# pcb.net
KiCad netlist of a schematic drawn in EAGLE
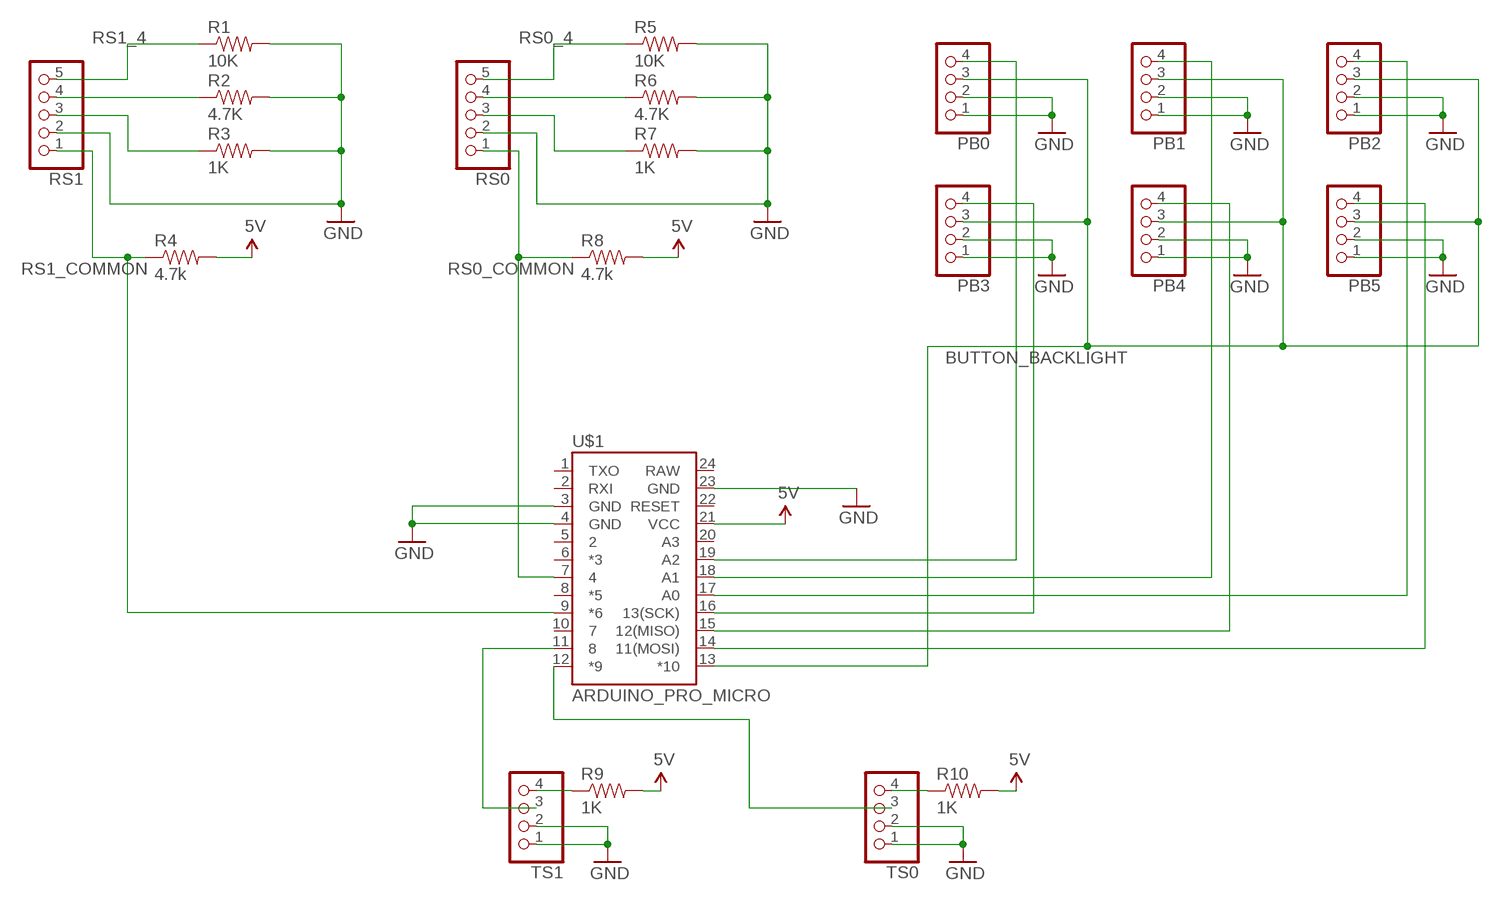
[diagram p0: schematic, sheet 1]

(export (version "E")
  (design (tool "Eeschema 10.0.6"))
  (components
    (comp (ref "PB0")
      (value "PINHD-1X4")
      (footprint "eagle-import:1X04")
      (libsource (lib "eagle-import") (part "PINHD-1X4"))
    )
    (comp (ref "PB1")
      (value "PINHD-1X4")
      (footprint "eagle-import:1X04")
      (libsource (lib "eagle-import") (part "PINHD-1X4"))
    )
    (comp (ref "PB2")
      (value "PINHD-1X4")
      (footprint "eagle-import:1X04")
      (libsource (lib "eagle-import") (part "PINHD-1X4"))
    )
    (comp (ref "PB3")
      (value "PINHD-1X4")
      (footprint "eagle-import:1X04")
      (libsource (lib "eagle-import") (part "PINHD-1X4"))
    )
    (comp (ref "PB4")
      (value "PINHD-1X4")
      (footprint "eagle-import:1X04")
      (libsource (lib "eagle-import") (part "PINHD-1X4"))
    )
    (comp (ref "PB5")
      (value "PINHD-1X4")
      (footprint "eagle-import:1X04")
      (libsource (lib "eagle-import") (part "PINHD-1X4"))
    )
    (comp (ref "R1")
      (value "10K")
      (footprint "eagle-import:AXIAL-0.3EZ")
      (libsource (lib "eagle-import") (part "1KOHM-1/4W-1%(PTH)HORIZ-KIT"))
    )
    (comp (ref "R2")
      (value "4.7K")
      (footprint "eagle-import:AXIAL-0.3EZ")
      (libsource (lib "eagle-import") (part "1KOHM-1/4W-1%(PTH)HORIZ-KIT"))
    )
    (comp (ref "R3")
      (value "1K")
      (footprint "eagle-import:AXIAL-0.3EZ")
      (libsource (lib "eagle-import") (part "1KOHM-1/4W-1%(PTH)HORIZ-KIT"))
    )
    (comp (ref "R4")
      (value "4.7k")
      (footprint "eagle-import:AXIAL-0.3EZ")
      (libsource (lib "eagle-import") (part "1KOHM-1/4W-1%(PTH)HORIZ-KIT"))
    )
    (comp (ref "R5")
      (value "10K")
      (footprint "eagle-import:AXIAL-0.3EZ")
      (libsource (lib "eagle-import") (part "1KOHM-1/4W-1%(PTH)HORIZ-KIT"))
    )
    (comp (ref "R6")
      (value "4.7K")
      (footprint "eagle-import:AXIAL-0.3EZ")
      (libsource (lib "eagle-import") (part "1KOHM-1/4W-1%(PTH)HORIZ-KIT"))
    )
    (comp (ref "R7")
      (value "1K")
      (footprint "eagle-import:AXIAL-0.3EZ")
      (libsource (lib "eagle-import") (part "1KOHM-1/4W-1%(PTH)HORIZ-KIT"))
    )
    (comp (ref "R8")
      (value "4.7k")
      (footprint "eagle-import:AXIAL-0.3EZ")
      (libsource (lib "eagle-import") (part "1KOHM-1/4W-1%(PTH)HORIZ-KIT"))
    )
    (comp (ref "R9")
      (value "1K")
      (footprint "eagle-import:AXIAL-0.3EZ")
      (libsource (lib "eagle-import") (part "1KOHM-1/4W-1%(PTH)HORIZ-KIT"))
    )
    (comp (ref "R10")
      (value "1K")
      (footprint "eagle-import:AXIAL-0.3EZ")
      (libsource (lib "eagle-import") (part "1KOHM-1/4W-1%(PTH)HORIZ-KIT"))
    )
    (comp (ref "RS0")
      (value "PINHD-1X5")
      (footprint "eagle-import:1X05")
      (libsource (lib "eagle-import") (part "PINHD-1X5"))
    )
    (comp (ref "RS1")
      (value "PINHD-1X5")
      (footprint "eagle-import:1X05")
      (libsource (lib "eagle-import") (part "PINHD-1X5"))
    )
    (comp (ref "TS0")
      (value "PINHD-1X4")
      (footprint "eagle-import:1X04")
      (libsource (lib "eagle-import") (part "PINHD-1X4"))
    )
    (comp (ref "TS1")
      (value "PINHD-1X4")
      (footprint "eagle-import:1X04")
      (libsource (lib "eagle-import") (part "PINHD-1X4"))
    )
    (comp (ref "U$1")
      (value "ARDUINO_PRO_MICRO")
      (footprint "eagle-import:ARDUINO_PRO_MICRO")
      (libsource (lib "eagle-import") (part "ARDUINO_PRO_MICRO"))
    )
  )
  (nets
    (net (code "1") (name "/BUTTON_BACKLIGHT") (class "Default")
      (node (ref "PB0") (pin "3") (pinfunction "3_3") (pintype "passive"))
      (node (ref "PB1") (pin "3") (pinfunction "3_3") (pintype "passive"))
      (node (ref "PB2") (pin "3") (pinfunction "3_3") (pintype "passive"))
      (node (ref "PB3") (pin "3") (pinfunction "3_3") (pintype "passive"))
      (node (ref "PB4") (pin "3") (pinfunction "3_3") (pintype "passive"))
      (node (ref "PB5") (pin "3") (pinfunction "3_3") (pintype "passive"))
      (node (ref "U$1") (pin "13") (pinfunction "*10_13") (pintype "bidirectional"))
    )
    (net (code "2") (name "/RS0_4") (class "Default")
      (node (ref "R5") (pin "P$1") (pinfunction "1_P$1") (pintype "passive"))
      (node (ref "RS0") (pin "5") (pinfunction "5_5") (pintype "passive"))
    )
    (net (code "3") (name "/RS0_COMMON") (class "Default")
      (node (ref "R8") (pin "P$1") (pinfunction "1_P$1") (pintype "passive"))
      (node (ref "RS0") (pin "1") (pinfunction "1_1") (pintype "passive"))
      (node (ref "U$1") (pin "7") (pinfunction "4_7") (pintype "bidirectional"))
    )
    (net (code "4") (name "/RS1_4") (class "Default")
      (node (ref "R1") (pin "P$1") (pinfunction "1_P$1") (pintype "passive"))
      (node (ref "RS1") (pin "5") (pinfunction "5_5") (pintype "passive"))
    )
    (net (code "5") (name "/RS1_COMMON") (class "Default")
      (node (ref "R4") (pin "P$1") (pinfunction "1_P$1") (pintype "passive"))
      (node (ref "RS1") (pin "1") (pinfunction "1_1") (pintype "passive"))
      (node (ref "U$1") (pin "9") (pinfunction "*6_9") (pintype "bidirectional"))
    )
    (net (code "6") (name "5V") (class "Default")
      (node (ref "R10") (pin "P$2") (pinfunction "2_P$2") (pintype "passive"))
      (node (ref "R4") (pin "P$2") (pinfunction "2_P$2") (pintype "passive"))
      (node (ref "R8") (pin "P$2") (pinfunction "2_P$2") (pintype "passive"))
      (node (ref "R9") (pin "P$2") (pinfunction "2_P$2") (pintype "passive"))
      (node (ref "U$1") (pin "21") (pinfunction "VCC_21") (pintype "bidirectional"))
    )
    (net (code "7") (name "GND") (class "Default")
      (node (ref "PB0") (pin "1") (pinfunction "1_1") (pintype "passive"))
      (node (ref "PB0") (pin "2") (pinfunction "2_2") (pintype "passive"))
      (node (ref "PB1") (pin "1") (pinfunction "1_1") (pintype "passive"))
      (node (ref "PB1") (pin "2") (pinfunction "2_2") (pintype "passive"))
      (node (ref "PB2") (pin "1") (pinfunction "1_1") (pintype "passive"))
      (node (ref "PB2") (pin "2") (pinfunction "2_2") (pintype "passive"))
      (node (ref "PB3") (pin "1") (pinfunction "1_1") (pintype "passive"))
      (node (ref "PB3") (pin "2") (pinfunction "2_2") (pintype "passive"))
      (node (ref "PB4") (pin "1") (pinfunction "1_1") (pintype "passive"))
      (node (ref "PB4") (pin "2") (pinfunction "2_2") (pintype "passive"))
      (node (ref "PB5") (pin "1") (pinfunction "1_1") (pintype "passive"))
      (node (ref "PB5") (pin "2") (pinfunction "2_2") (pintype "passive"))
      (node (ref "R1") (pin "P$2") (pinfunction "2_P$2") (pintype "passive"))
      (node (ref "R2") (pin "P$2") (pinfunction "2_P$2") (pintype "passive"))
      (node (ref "R3") (pin "P$2") (pinfunction "2_P$2") (pintype "passive"))
      (node (ref "R5") (pin "P$2") (pinfunction "2_P$2") (pintype "passive"))
      (node (ref "R6") (pin "P$2") (pinfunction "2_P$2") (pintype "passive"))
      (node (ref "R7") (pin "P$2") (pinfunction "2_P$2") (pintype "passive"))
      (node (ref "RS0") (pin "2") (pinfunction "2_2") (pintype "passive"))
      (node (ref "RS1") (pin "2") (pinfunction "2_2") (pintype "passive"))
      (node (ref "TS0") (pin "1") (pinfunction "1_1") (pintype "passive"))
      (node (ref "TS0") (pin "2") (pinfunction "2_2") (pintype "passive"))
      (node (ref "TS1") (pin "1") (pinfunction "1_1") (pintype "passive"))
      (node (ref "TS1") (pin "2") (pinfunction "2_2") (pintype "passive"))
      (node (ref "U$1") (pin "23") (pinfunction "GND_23") (pintype "bidirectional"))
      (node (ref "U$1") (pin "3") (pinfunction "GND_3") (pintype "bidirectional"))
      (node (ref "U$1") (pin "4") (pinfunction "GND_4") (pintype "bidirectional"))
    )
    (net (code "8") (name "Net-(R2-1)") (class "Default")
      (node (ref "R2") (pin "P$1") (pinfunction "1_P$1") (pintype "passive"))
      (node (ref "RS1") (pin "4") (pinfunction "4_4") (pintype "passive"))
    )
    (net (code "9") (name "Net-(R3-1)") (class "Default")
      (node (ref "R3") (pin "P$1") (pinfunction "1_P$1") (pintype "passive"))
      (node (ref "RS1") (pin "3") (pinfunction "3_3") (pintype "passive"))
    )
    (net (code "10") (name "Net-(R6-1)") (class "Default")
      (node (ref "R6") (pin "P$1") (pinfunction "1_P$1") (pintype "passive"))
      (node (ref "RS0") (pin "4") (pinfunction "4_4") (pintype "passive"))
    )
    (net (code "11") (name "Net-(R7-1)") (class "Default")
      (node (ref "R7") (pin "P$1") (pinfunction "1_P$1") (pintype "passive"))
      (node (ref "RS0") (pin "3") (pinfunction "3_3") (pintype "passive"))
    )
    (net (code "12") (name "Net-(R9-1)") (class "Default")
      (node (ref "R9") (pin "P$1") (pinfunction "1_P$1") (pintype "passive"))
      (node (ref "TS1") (pin "4") (pinfunction "4_4") (pintype "passive"))
    )
    (net (code "13") (name "Net-(R10-1)") (class "Default")
      (node (ref "R10") (pin "P$1") (pinfunction "1_P$1") (pintype "passive"))
      (node (ref "TS0") (pin "4") (pinfunction "4_4") (pintype "passive"))
    )
    (net (code "14") (name "Net-(U$1-*9)") (class "Default")
      (node (ref "TS0") (pin "3") (pinfunction "3_3") (pintype "passive"))
      (node (ref "U$1") (pin "12") (pinfunction "*9_12") (pintype "bidirectional"))
    )
    (net (code "15") (name "Net-(U$1-8)") (class "Default")
      (node (ref "TS1") (pin "3") (pinfunction "3_3") (pintype "passive"))
      (node (ref "U$1") (pin "11") (pinfunction "8_11") (pintype "bidirectional"))
    )
    (net (code "16") (name "Net-(U$1-11(MOSI))") (class "Default")
      (node (ref "PB5") (pin "4") (pinfunction "4_4") (pintype "passive"))
      (node (ref "U$1") (pin "14") (pinfunction "11(MOSI)_14") (pintype "bidirectional"))
    )
    (net (code "17") (name "Net-(U$1-12(MISO))") (class "Default")
      (node (ref "PB4") (pin "4") (pinfunction "4_4") (pintype "passive"))
      (node (ref "U$1") (pin "15") (pinfunction "12(MISO)_15") (pintype "bidirectional"))
    )
    (net (code "18") (name "Net-(U$1-13(SCK))") (class "Default")
      (node (ref "PB3") (pin "4") (pinfunction "4_4") (pintype "passive"))
      (node (ref "U$1") (pin "16") (pinfunction "13(SCK)_16") (pintype "bidirectional"))
    )
    (net (code "19") (name "Net-(U$1-A0)") (class "Default")
      (node (ref "PB2") (pin "4") (pinfunction "4_4") (pintype "passive"))
      (node (ref "U$1") (pin "17") (pinfunction "A0_17") (pintype "bidirectional"))
    )
    (net (code "20") (name "Net-(U$1-A1)") (class "Default")
      (node (ref "PB1") (pin "4") (pinfunction "4_4") (pintype "passive"))
      (node (ref "U$1") (pin "18") (pinfunction "A1_18") (pintype "bidirectional"))
    )
    (net (code "21") (name "Net-(U$1-A2)") (class "Default")
      (node (ref "PB0") (pin "4") (pinfunction "4_4") (pintype "passive"))
      (node (ref "U$1") (pin "19") (pinfunction "A2_19") (pintype "bidirectional"))
    )
    (net (code "22") (name "unconnected-(U$1-*3-Pad6)") (class "Default")
      (node (ref "U$1") (pin "6") (pinfunction "*3_6") (pintype "bidirectional"))
    )
    (net (code "23") (name "unconnected-(U$1-*5-Pad8)") (class "Default")
      (node (ref "U$1") (pin "8") (pinfunction "*5_8") (pintype "bidirectional"))
    )
    (net (code "24") (name "unconnected-(U$1-2-Pad5)") (class "Default")
      (node (ref "U$1") (pin "5") (pinfunction "2_5") (pintype "bidirectional"))
    )
    (net (code "25") (name "unconnected-(U$1-7-Pad10)") (class "Default")
      (node (ref "U$1") (pin "10") (pinfunction "7_10") (pintype "bidirectional"))
    )
    (net (code "26") (name "unconnected-(U$1-A3-Pad20)") (class "Default")
      (node (ref "U$1") (pin "20") (pinfunction "A3_20") (pintype "bidirectional"))
    )
    (net (code "27") (name "unconnected-(U$1-RAW-Pad24)") (class "Default")
      (node (ref "U$1") (pin "24") (pinfunction "RAW_24") (pintype "bidirectional"))
    )
    (net (code "28") (name "unconnected-(U$1-RESET-Pad22)") (class "Default")
      (node (ref "U$1") (pin "22") (pinfunction "RESET_22") (pintype "bidirectional"))
    )
    (net (code "29") (name "unconnected-(U$1-RXI-Pad2)") (class "Default")
      (node (ref "U$1") (pin "2") (pinfunction "RXI_2") (pintype "bidirectional"))
    )
    (net (code "30") (name "unconnected-(U$1-TXO-Pad1)") (class "Default")
      (node (ref "U$1") (pin "1") (pinfunction "TXO_1") (pintype "bidirectional"))
    )
  )
)
